# RoPi_2560.net
KiCad netlist of a schematic drawn in EAGLE
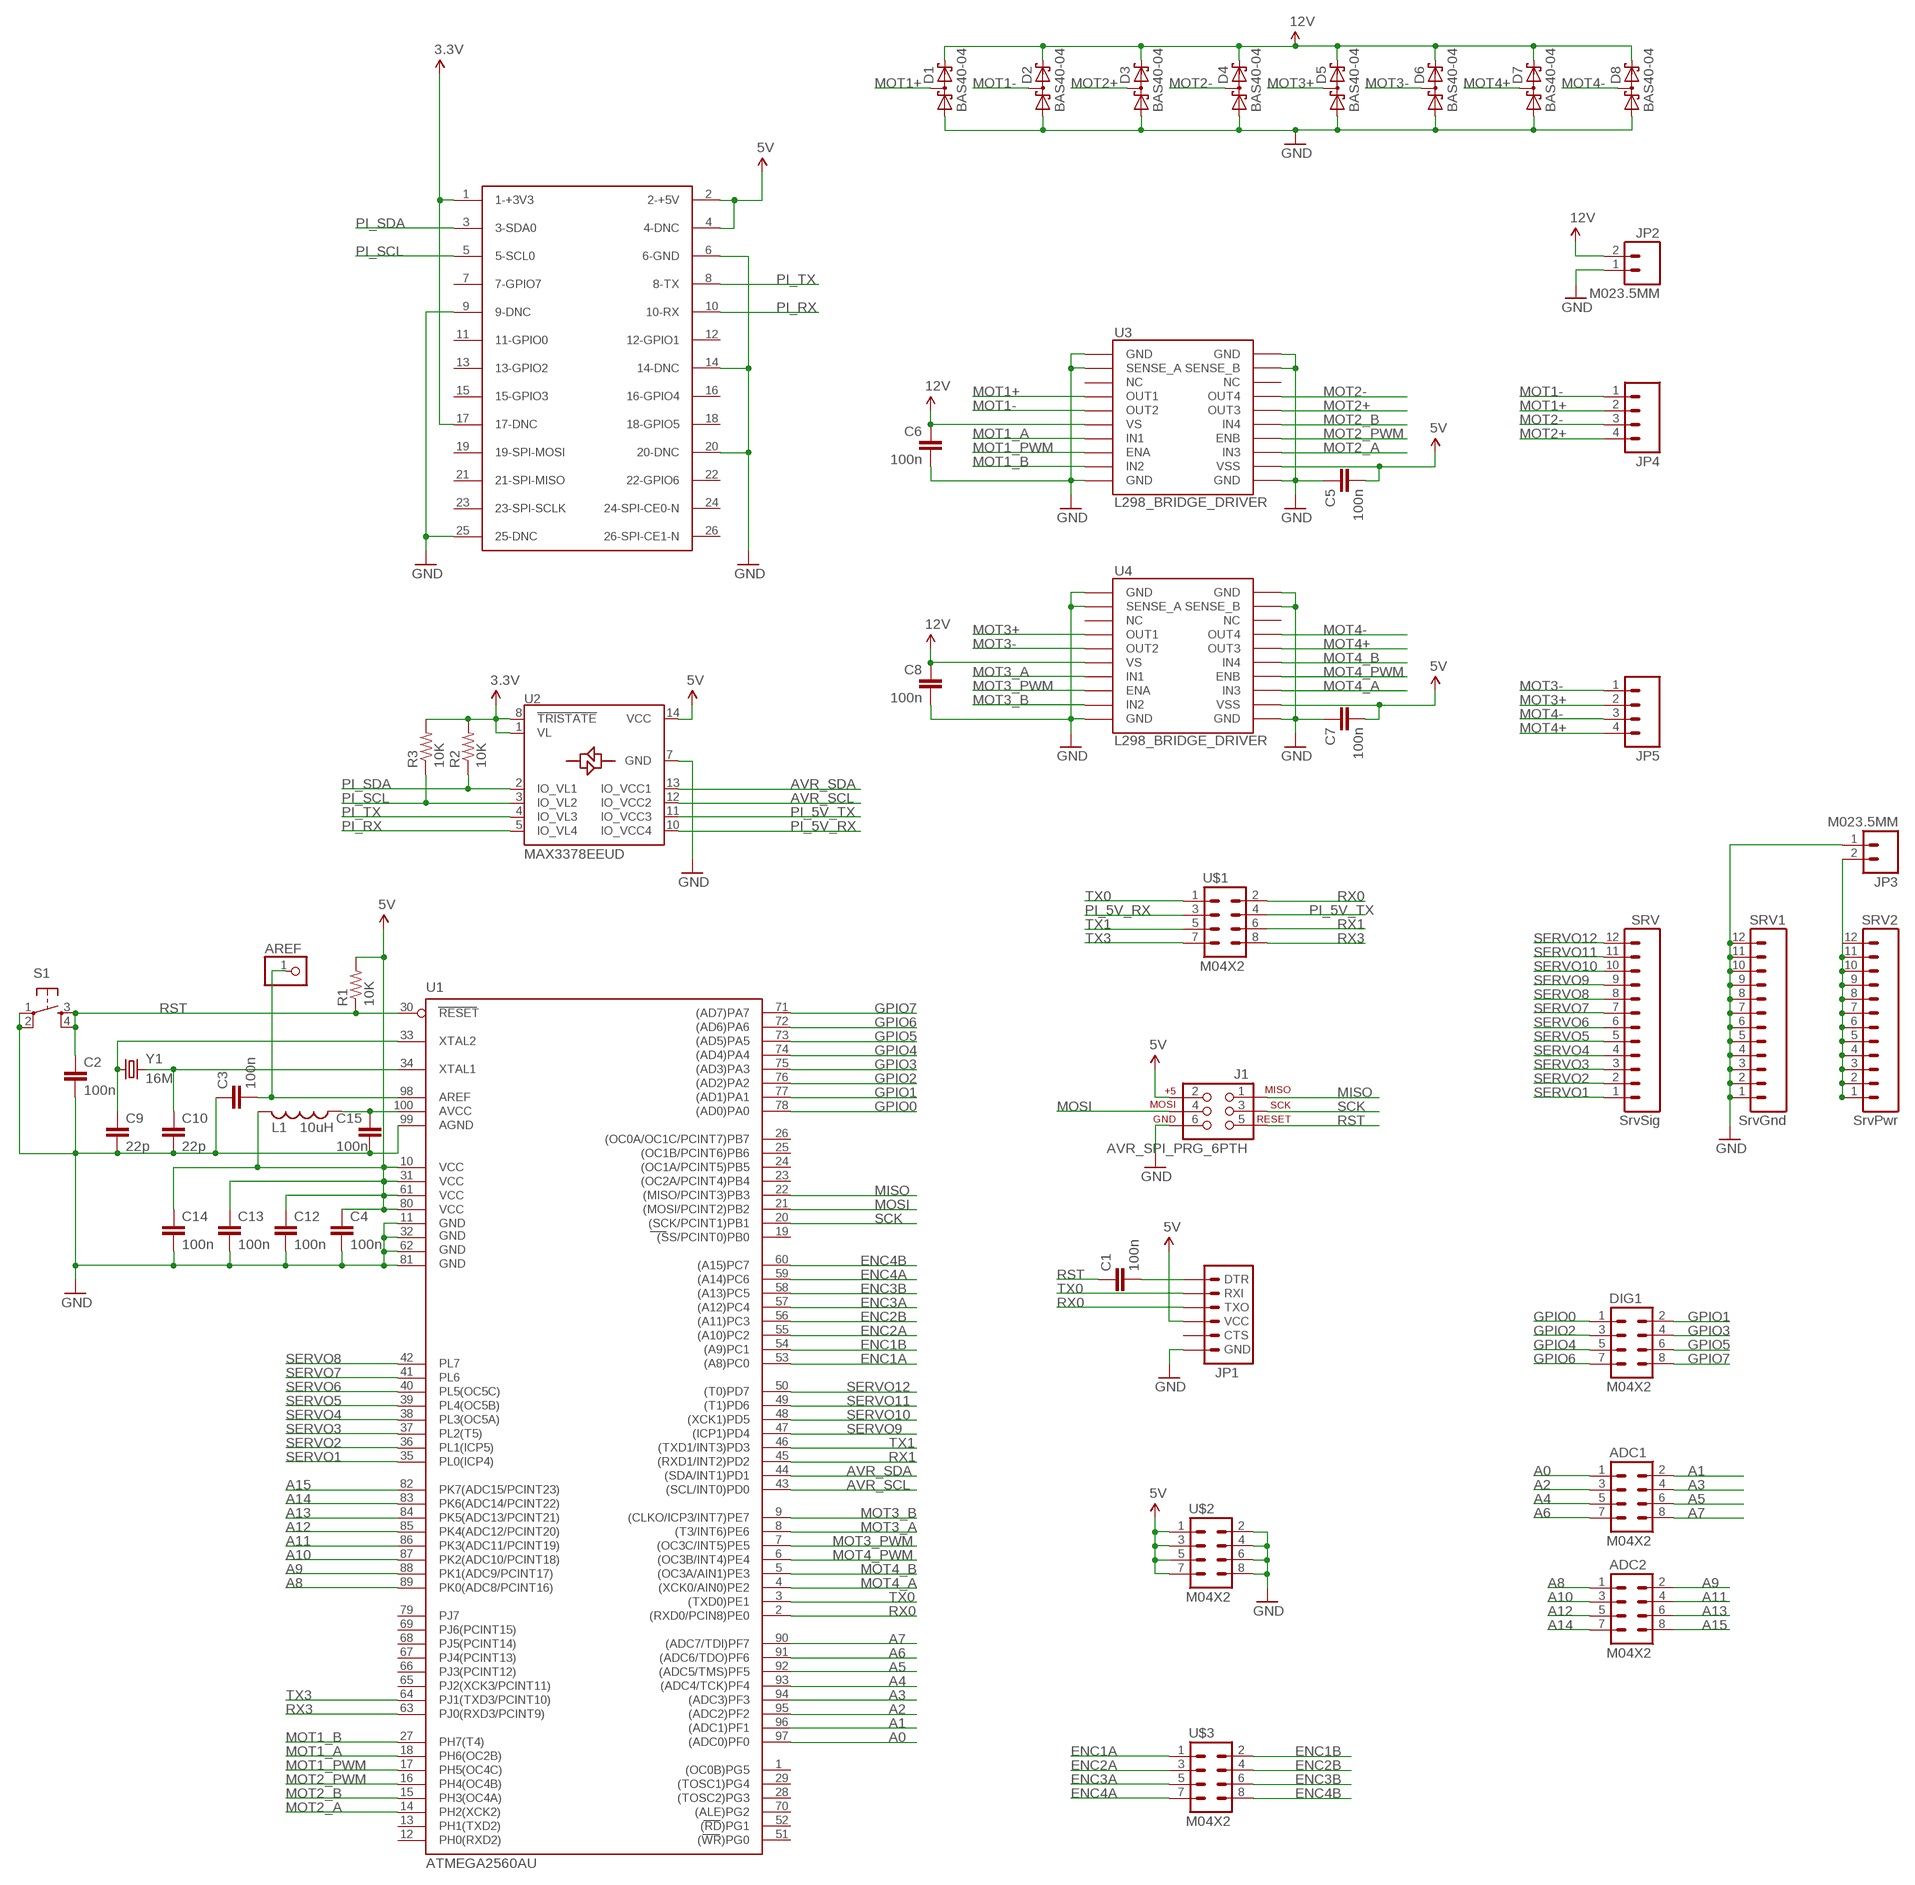
[diagram p0: schematic, sheet 1]

(export (version "E")
  (design (tool "Eeschema 10.0.6"))
  (components
    (comp (ref "ADC1")
      (value "M04X2")
      (footprint "eagle-import:2X4")
      (libsource (lib "eagle-import") (part "M04X2"))
    )
    (comp (ref "ADC2")
      (value "M04X2")
      (footprint "eagle-import:2X4")
      (libsource (lib "eagle-import") (part "M04X2"))
    )
    (comp (ref "AREF")
      (value "PINHD-1X1")
      (footprint "eagle-import:1X01")
      (libsource (lib "eagle-import") (part "PINHD-1X1"))
    )
    (comp (ref "C1")
      (value "100n")
      (footprint "eagle-import:0603-CAP")
      (libsource (lib "eagle-import") (part "CAP0603-CAP"))
    )
    (comp (ref "C2")
      (value "100n")
      (footprint "eagle-import:0603-CAP")
      (libsource (lib "eagle-import") (part "CAP0603-CAP"))
    )
    (comp (ref "C3")
      (value "100n")
      (footprint "eagle-import:0603-CAP")
      (libsource (lib "eagle-import") (part "CAP0603-CAP"))
    )
    (comp (ref "C4")
      (value "100n")
      (footprint "eagle-import:0603-CAP")
      (libsource (lib "eagle-import") (part "CAP0603-CAP"))
    )
    (comp (ref "C5")
      (value "100n")
      (footprint "eagle-import:0603-CAP")
      (libsource (lib "eagle-import") (part "CAP0603-CAP"))
    )
    (comp (ref "C6")
      (value "100n")
      (footprint "eagle-import:0603-CAP")
      (libsource (lib "eagle-import") (part "CAP0603-CAP"))
    )
    (comp (ref "C7")
      (value "100n")
      (footprint "eagle-import:0603-CAP")
      (libsource (lib "eagle-import") (part "CAP0603-CAP"))
    )
    (comp (ref "C8")
      (value "100n")
      (footprint "eagle-import:0603-CAP")
      (libsource (lib "eagle-import") (part "CAP0603-CAP"))
    )
    (comp (ref "C9")
      (value "22p")
      (footprint "eagle-import:0603-CAP")
      (libsource (lib "eagle-import") (part "CAP0603-CAP"))
    )
    (comp (ref "C10")
      (value "22p")
      (footprint "eagle-import:0603-CAP")
      (libsource (lib "eagle-import") (part "CAP0603-CAP"))
    )
    (comp (ref "C12")
      (value "100n")
      (footprint "eagle-import:0603-CAP")
      (libsource (lib "eagle-import") (part "CAP0603-CAP"))
    )
    (comp (ref "C13")
      (value "100n")
      (footprint "eagle-import:0603-CAP")
      (libsource (lib "eagle-import") (part "CAP0603-CAP"))
    )
    (comp (ref "C14")
      (value "100n")
      (footprint "eagle-import:0603-CAP")
      (libsource (lib "eagle-import") (part "CAP0603-CAP"))
    )
    (comp (ref "C15")
      (value "100n")
      (footprint "eagle-import:0603-CAP")
      (libsource (lib "eagle-import") (part "CAP0603-CAP"))
    )
    (comp (ref "D1")
      (value "BAS40-04")
      (footprint "eagle-import:SOT23")
      (libsource (lib "eagle-import") (part "BAS40-04"))
    )
    (comp (ref "D2")
      (value "BAS40-04")
      (footprint "eagle-import:SOT23")
      (libsource (lib "eagle-import") (part "BAS40-04"))
    )
    (comp (ref "D3")
      (value "BAS40-04")
      (footprint "eagle-import:SOT23")
      (libsource (lib "eagle-import") (part "BAS40-04"))
    )
    (comp (ref "D4")
      (value "BAS40-04")
      (footprint "eagle-import:SOT23")
      (libsource (lib "eagle-import") (part "BAS40-04"))
    )
    (comp (ref "D5")
      (value "BAS40-04")
      (footprint "eagle-import:SOT23")
      (libsource (lib "eagle-import") (part "BAS40-04"))
    )
    (comp (ref "D6")
      (value "BAS40-04")
      (footprint "eagle-import:SOT23")
      (libsource (lib "eagle-import") (part "BAS40-04"))
    )
    (comp (ref "D7")
      (value "BAS40-04")
      (footprint "eagle-import:SOT23")
      (libsource (lib "eagle-import") (part "BAS40-04"))
    )
    (comp (ref "D8")
      (value "BAS40-04")
      (footprint "eagle-import:SOT23")
      (libsource (lib "eagle-import") (part "BAS40-04"))
    )
    (comp (ref "DIG1")
      (value "M04X2")
      (footprint "eagle-import:2X4")
      (libsource (lib "eagle-import") (part "M04X2"))
    )
    (comp (ref "J1")
      (value "AVR_SPI_PRG_6PTH")
      (footprint "eagle-import:2X3")
      (libsource (lib "eagle-import") (part "AVR_SPI_PRG_6PTH"))
    )
    (comp (ref "JP1")
      (value "ARDUINO_SERIAL_PROGRAMSMD")
      (footprint "eagle-import:1X06-SMD")
      (libsource (lib "eagle-import") (part "ARDUINO_SERIAL_PROGRAMSMD"))
    )
    (comp (ref "JP2")
      (value "M023.5MM")
      (footprint "eagle-import:SCREWTERMINAL-3.5MM-2")
      (libsource (lib "eagle-import") (part "M023.5MM"))
    )
    (comp (ref "JP3")
      (value "M023.5MM")
      (footprint "eagle-import:SCREWTERMINAL-3.5MM-2")
      (libsource (lib "eagle-import") (part "M023.5MM"))
    )
    (comp (ref "JP4")
      (value "M04SCREW")
      (footprint "eagle-import:SCREWTERMINAL-3.5MM-4")
      (libsource (lib "eagle-import") (part "M04SCREW"))
    )
    (comp (ref "JP5")
      (value "M04SCREW")
      (footprint "eagle-import:SCREWTERMINAL-3.5MM-4")
      (libsource (lib "eagle-import") (part "M04SCREW"))
    )
    (comp (ref "L1")
      (value "10uH")
      (footprint "eagle-import:R0603")
      (libsource (lib "eagle-import") (part "L-US"))
    )
    (comp (ref "PI")
      (value "RASPBERRY-PI")
      (footprint "eagle-import:RASPBERRY-PI")
      (libsource (lib "eagle-import") (part "RASPBERRY-PI"))
    )
    (comp (ref "R1")
      (value "10K")
      (footprint "eagle-import:0603-RES")
      (libsource (lib "eagle-import") (part "RESISTOR0603-RES"))
    )
    (comp (ref "R2")
      (value "10K")
      (footprint "eagle-import:0603-RES")
      (libsource (lib "eagle-import") (part "RESISTOR0603-RES"))
    )
    (comp (ref "R3")
      (value "10K")
      (footprint "eagle-import:0603-RES")
      (libsource (lib "eagle-import") (part "RESISTOR0603-RES"))
    )
    (comp (ref "S1")
      (value "TAC_SWITCHSMD")
      (footprint "eagle-import:TACTILE_SWITCH_SMD")
      (libsource (lib "eagle-import") (part "TAC_SWITCHSMD"))
    )
    (comp (ref "SRV")
      (value "SrvSig")
      (footprint "eagle-import:1X12")
      (libsource (lib "eagle-import") (part "M12PTH"))
    )
    (comp (ref "SRV1")
      (value "SrvGnd")
      (footprint "eagle-import:1X12")
      (libsource (lib "eagle-import") (part "M12PTH"))
    )
    (comp (ref "SRV2")
      (value "SrvPwr")
      (footprint "eagle-import:1X12")
      (libsource (lib "eagle-import") (part "M12PTH"))
    )
    (comp (ref "U$1")
      (value "M04X2")
      (footprint "eagle-import:2X4")
      (libsource (lib "eagle-import") (part "M04X2"))
    )
    (comp (ref "U$2")
      (value "M04X2")
      (footprint "eagle-import:2X4")
      (libsource (lib "eagle-import") (part "M04X2"))
    )
    (comp (ref "U$3")
      (value "M04X2")
      (footprint "eagle-import:2X4")
      (libsource (lib "eagle-import") (part "M04X2"))
    )
    (comp (ref "U1")
      (value "ATMEGA2560AU")
      (footprint "eagle-import:TQFP100")
      (libsource (lib "eagle-import") (part "ATMEGA2560AU"))
    )
    (comp (ref "U2")
      (value "MAX3378EEUD")
      (footprint "eagle-import:TSSOP14")
      (libsource (lib "eagle-import") (part "MAX3378EEUD"))
    )
    (comp (ref "U3")
      (value "L298_BRIDGE_DRIVER")
      (footprint "eagle-import:POWERSO20")
      (libsource (lib "eagle-import") (part "L298_BRIDGE_DRIVER"))
    )
    (comp (ref "U4")
      (value "L298_BRIDGE_DRIVER")
      (footprint "eagle-import:POWERSO20")
      (libsource (lib "eagle-import") (part "L298_BRIDGE_DRIVER"))
    )
    (comp (ref "Y1")
      (value "16M")
      (footprint "eagle-import:HC49UP")
      (libsource (lib "eagle-import") (part "CRYSTALSMD"))
    )
  )
  (nets
    (net (code "1") (name "/A0") (class "Default")
      (node (ref "ADC1") (pin "1") (pinfunction "1_1") (pintype "passive"))
      (node (ref "U1") (pin "97") (pinfunction "(ADC0)PF0_97") (pintype "bidirectional"))
    )
    (net (code "2") (name "/A1") (class "Default")
      (node (ref "ADC1") (pin "2") (pinfunction "2_2") (pintype "passive"))
      (node (ref "U1") (pin "96") (pinfunction "(ADC1)PF1_96") (pintype "bidirectional"))
    )
    (net (code "3") (name "/A2") (class "Default")
      (node (ref "ADC1") (pin "3") (pinfunction "3_3") (pintype "passive"))
      (node (ref "U1") (pin "95") (pinfunction "(ADC2)PF2_95") (pintype "bidirectional"))
    )
    (net (code "4") (name "/A3") (class "Default")
      (node (ref "ADC1") (pin "4") (pinfunction "4_4") (pintype "passive"))
      (node (ref "U1") (pin "94") (pinfunction "(ADC3)PF3_94") (pintype "bidirectional"))
    )
    (net (code "5") (name "/A4") (class "Default")
      (node (ref "ADC1") (pin "5") (pinfunction "5_5") (pintype "passive"))
      (node (ref "U1") (pin "93") (pinfunction "(ADC4/TCK)PF4_93") (pintype "bidirectional"))
    )
    (net (code "6") (name "/A5") (class "Default")
      (node (ref "ADC1") (pin "6") (pinfunction "6_6") (pintype "passive"))
      (node (ref "U1") (pin "92") (pinfunction "(ADC5/TMS)PF5_92") (pintype "bidirectional"))
    )
    (net (code "7") (name "/A6") (class "Default")
      (node (ref "ADC1") (pin "7") (pinfunction "7_7") (pintype "passive"))
      (node (ref "U1") (pin "91") (pinfunction "(ADC6/TDO)PF6_91") (pintype "bidirectional"))
    )
    (net (code "8") (name "/A7") (class "Default")
      (node (ref "ADC1") (pin "8") (pinfunction "8_8") (pintype "passive"))
      (node (ref "U1") (pin "90") (pinfunction "(ADC7/TDI)PF7_90") (pintype "bidirectional"))
    )
    (net (code "9") (name "/A8") (class "Default")
      (node (ref "ADC2") (pin "1") (pinfunction "1_1") (pintype "passive"))
      (node (ref "U1") (pin "89") (pinfunction "PK0(ADC8/PCINT16)_89") (pintype "bidirectional"))
    )
    (net (code "10") (name "/A9") (class "Default")
      (node (ref "ADC2") (pin "2") (pinfunction "2_2") (pintype "passive"))
      (node (ref "U1") (pin "88") (pinfunction "PK1(ADC9/PCINT17)_88") (pintype "bidirectional"))
    )
    (net (code "11") (name "/A10") (class "Default")
      (node (ref "ADC2") (pin "3") (pinfunction "3_3") (pintype "passive"))
      (node (ref "U1") (pin "87") (pinfunction "PK2(ADC10/PCINT18)_87") (pintype "bidirectional"))
    )
    (net (code "12") (name "/A11") (class "Default")
      (node (ref "ADC2") (pin "4") (pinfunction "4_4") (pintype "passive"))
      (node (ref "U1") (pin "86") (pinfunction "PK3(ADC11/PCINT19)_86") (pintype "bidirectional"))
    )
    (net (code "13") (name "/A12") (class "Default")
      (node (ref "ADC2") (pin "5") (pinfunction "5_5") (pintype "passive"))
      (node (ref "U1") (pin "85") (pinfunction "PK4(ADC12/PCINT20)_85") (pintype "bidirectional"))
    )
    (net (code "14") (name "/A13") (class "Default")
      (node (ref "ADC2") (pin "6") (pinfunction "6_6") (pintype "passive"))
      (node (ref "U1") (pin "84") (pinfunction "PK5(ADC13/PCINT21)_84") (pintype "bidirectional"))
    )
    (net (code "15") (name "/A14") (class "Default")
      (node (ref "ADC2") (pin "7") (pinfunction "7_7") (pintype "passive"))
      (node (ref "U1") (pin "83") (pinfunction "PK6(ADC14/PCINT22)_83") (pintype "bidirectional"))
    )
    (net (code "16") (name "/A15") (class "Default")
      (node (ref "ADC2") (pin "8") (pinfunction "8_8") (pintype "passive"))
      (node (ref "U1") (pin "82") (pinfunction "PK7(ADC15/PCINT23)_82") (pintype "bidirectional"))
    )
    (net (code "17") (name "/AVR_SCL") (class "Default")
      (node (ref "U1") (pin "43") (pinfunction "(SCL/INT0)PD0_43") (pintype "bidirectional"))
      (node (ref "U2") (pin "12") (pinfunction "IO_VCC2_12") (pintype "bidirectional"))
    )
    (net (code "18") (name "/AVR_SDA") (class "Default")
      (node (ref "U1") (pin "44") (pinfunction "(SDA/INT1)PD1_44") (pintype "bidirectional"))
      (node (ref "U2") (pin "13") (pinfunction "IO_VCC1_13") (pintype "bidirectional"))
    )
    (net (code "19") (name "/ENC1A") (class "Default")
      (node (ref "U$3") (pin "1") (pinfunction "1_1") (pintype "passive"))
      (node (ref "U1") (pin "53") (pinfunction "(A8)PC0_53") (pintype "bidirectional"))
    )
    (net (code "20") (name "/ENC1B") (class "Default")
      (node (ref "U$3") (pin "2") (pinfunction "2_2") (pintype "passive"))
      (node (ref "U1") (pin "54") (pinfunction "(A9)PC1_54") (pintype "bidirectional"))
    )
    (net (code "21") (name "/ENC2A") (class "Default")
      (node (ref "U$3") (pin "3") (pinfunction "3_3") (pintype "passive"))
      (node (ref "U1") (pin "55") (pinfunction "(A10)PC2_55") (pintype "bidirectional"))
    )
    (net (code "22") (name "/ENC2B") (class "Default")
      (node (ref "U$3") (pin "4") (pinfunction "4_4") (pintype "passive"))
      (node (ref "U1") (pin "56") (pinfunction "(A11)PC3_56") (pintype "bidirectional"))
    )
    (net (code "23") (name "/ENC3A") (class "Default")
      (node (ref "U$3") (pin "5") (pinfunction "5_5") (pintype "passive"))
      (node (ref "U1") (pin "57") (pinfunction "(A12)PC4_57") (pintype "bidirectional"))
    )
    (net (code "24") (name "/ENC3B") (class "Default")
      (node (ref "U$3") (pin "6") (pinfunction "6_6") (pintype "passive"))
      (node (ref "U1") (pin "58") (pinfunction "(A13)PC5_58") (pintype "bidirectional"))
    )
    (net (code "25") (name "/ENC4A") (class "Default")
      (node (ref "U$3") (pin "7") (pinfunction "7_7") (pintype "passive"))
      (node (ref "U1") (pin "59") (pinfunction "(A14)PC6_59") (pintype "bidirectional"))
    )
    (net (code "26") (name "/ENC4B") (class "Default")
      (node (ref "U$3") (pin "8") (pinfunction "8_8") (pintype "passive"))
      (node (ref "U1") (pin "60") (pinfunction "(A15)PC7_60") (pintype "bidirectional"))
    )
    (net (code "27") (name "/GPIO0") (class "Default")
      (node (ref "DIG1") (pin "1") (pinfunction "1_1") (pintype "passive"))
      (node (ref "U1") (pin "78") (pinfunction "(AD0)PA0_78") (pintype "bidirectional"))
    )
    (net (code "28") (name "/GPIO1") (class "Default")
      (node (ref "DIG1") (pin "2") (pinfunction "2_2") (pintype "passive"))
      (node (ref "U1") (pin "77") (pinfunction "(AD1)PA1_77") (pintype "bidirectional"))
    )
    (net (code "29") (name "/GPIO2") (class "Default")
      (node (ref "DIG1") (pin "3") (pinfunction "3_3") (pintype "passive"))
      (node (ref "U1") (pin "76") (pinfunction "(AD2)PA2_76") (pintype "bidirectional"))
    )
    (net (code "30") (name "/GPIO3") (class "Default")
      (node (ref "DIG1") (pin "4") (pinfunction "4_4") (pintype "passive"))
      (node (ref "U1") (pin "75") (pinfunction "(AD3)PA3_75") (pintype "bidirectional"))
    )
    (net (code "31") (name "/GPIO4") (class "Default")
      (node (ref "DIG1") (pin "5") (pinfunction "5_5") (pintype "passive"))
      (node (ref "U1") (pin "74") (pinfunction "(AD4)PA4_74") (pintype "bidirectional"))
    )
    (net (code "32") (name "/GPIO5") (class "Default")
      (node (ref "DIG1") (pin "6") (pinfunction "6_6") (pintype "passive"))
      (node (ref "U1") (pin "73") (pinfunction "(AD5)PA5_73") (pintype "bidirectional"))
    )
    (net (code "33") (name "/GPIO6") (class "Default")
      (node (ref "DIG1") (pin "7") (pinfunction "7_7") (pintype "passive"))
      (node (ref "U1") (pin "72") (pinfunction "(AD6)PA6_72") (pintype "bidirectional"))
    )
    (net (code "34") (name "/GPIO7") (class "Default")
      (node (ref "DIG1") (pin "8") (pinfunction "8_8") (pintype "passive"))
      (node (ref "U1") (pin "71") (pinfunction "(AD7)PA7_71") (pintype "bidirectional"))
    )
    (net (code "35") (name "/MISO") (class "Default")
      (node (ref "J1") (pin "1") (pinfunction "1_1") (pintype "passive"))
      (node (ref "U1") (pin "22") (pinfunction "(MISO/PCINT3)PB3_22") (pintype "bidirectional"))
    )
    (net (code "36") (name "/MOSI") (class "Default")
      (node (ref "J1") (pin "4") (pinfunction "4_4") (pintype "passive"))
      (node (ref "U1") (pin "21") (pinfunction "(MOSI/PCINT2)PB2_21") (pintype "bidirectional"))
    )
    (net (code "37") (name "/MOT1+") (class "Default")
      (node (ref "D1") (pin "3") (pinfunction "C1A2_3") (pintype "passive"))
      (node (ref "JP4") (pin "2") (pinfunction "2_2") (pintype "passive"))
      (node (ref "U3") (pin "4") (pinfunction "OUT1_4") (pintype "bidirectional"))
    )
    (net (code "38") (name "/MOT1-") (class "Default")
      (node (ref "D2") (pin "3") (pinfunction "C1A2_3") (pintype "passive"))
      (node (ref "JP4") (pin "1") (pinfunction "1_1") (pintype "passive"))
      (node (ref "U3") (pin "5") (pinfunction "OUT2_5") (pintype "bidirectional"))
    )
    (net (code "39") (name "/MOT1_A") (class "Default")
      (node (ref "U1") (pin "18") (pinfunction "PH6(OC2B)_18") (pintype "bidirectional"))
      (node (ref "U3") (pin "7") (pinfunction "IN1_7") (pintype "bidirectional"))
    )
    (net (code "40") (name "/MOT1_B") (class "Default")
      (node (ref "U1") (pin "27") (pinfunction "PH7(T4)_27") (pintype "bidirectional"))
      (node (ref "U3") (pin "9") (pinfunction "IN2_9") (pintype "bidirectional"))
    )
    (net (code "41") (name "/MOT1_PWM") (class "Default")
      (node (ref "U1") (pin "17") (pinfunction "PH5(OC4C)_17") (pintype "bidirectional"))
      (node (ref "U3") (pin "8") (pinfunction "ENA_8") (pintype "bidirectional"))
    )
    (net (code "42") (name "/MOT2+") (class "Default")
      (node (ref "D3") (pin "3") (pinfunction "C1A2_3") (pintype "passive"))
      (node (ref "JP4") (pin "4") (pinfunction "4_4") (pintype "passive"))
      (node (ref "U3") (pin "16") (pinfunction "OUT3_16") (pintype "bidirectional"))
    )
    (net (code "43") (name "/MOT2-") (class "Default")
      (node (ref "D4") (pin "3") (pinfunction "C1A2_3") (pintype "passive"))
      (node (ref "JP4") (pin "3") (pinfunction "3_3") (pintype "passive"))
      (node (ref "U3") (pin "17") (pinfunction "OUT4_17") (pintype "bidirectional"))
    )
    (net (code "44") (name "/MOT2_A") (class "Default")
      (node (ref "U1") (pin "14") (pinfunction "PH2(XCK2)_14") (pintype "bidirectional"))
      (node (ref "U3") (pin "13") (pinfunction "IN3_13") (pintype "bidirectional"))
    )
    (net (code "45") (name "/MOT2_B") (class "Default")
      (node (ref "U1") (pin "15") (pinfunction "PH3(OC4A)_15") (pintype "bidirectional"))
      (node (ref "U3") (pin "15") (pinfunction "IN4_15") (pintype "bidirectional"))
    )
    (net (code "46") (name "/MOT2_PWM") (class "Default")
      (node (ref "U1") (pin "16") (pinfunction "PH4(OC4B)_16") (pintype "bidirectional"))
      (node (ref "U3") (pin "14") (pinfunction "ENB_14") (pintype "bidirectional"))
    )
    (net (code "47") (name "/MOT3+") (class "Default")
      (node (ref "D5") (pin "3") (pinfunction "C1A2_3") (pintype "passive"))
      (node (ref "JP5") (pin "2") (pinfunction "2_2") (pintype "passive"))
      (node (ref "U4") (pin "4") (pinfunction "OUT1_4") (pintype "bidirectional"))
    )
    (net (code "48") (name "/MOT3-") (class "Default")
      (node (ref "D6") (pin "3") (pinfunction "C1A2_3") (pintype "passive"))
      (node (ref "JP5") (pin "1") (pinfunction "1_1") (pintype "passive"))
      (node (ref "U4") (pin "5") (pinfunction "OUT2_5") (pintype "bidirectional"))
    )
    (net (code "49") (name "/MOT3_A") (class "Default")
      (node (ref "U1") (pin "8") (pinfunction "(T3/INT6)PE6_8") (pintype "bidirectional"))
      (node (ref "U4") (pin "7") (pinfunction "IN1_7") (pintype "bidirectional"))
    )
    (net (code "50") (name "/MOT3_B") (class "Default")
      (node (ref "U1") (pin "9") (pinfunction "(CLKO/ICP3/INT7)PE7_9") (pintype "bidirectional"))
      (node (ref "U4") (pin "9") (pinfunction "IN2_9") (pintype "bidirectional"))
    )
    (net (code "51") (name "/MOT3_PWM") (class "Default")
      (node (ref "U1") (pin "7") (pinfunction "(OC3C/INT5)PE5_7") (pintype "bidirectional"))
      (node (ref "U4") (pin "8") (pinfunction "ENA_8") (pintype "bidirectional"))
    )
    (net (code "52") (name "/MOT4+") (class "Default")
      (node (ref "D7") (pin "3") (pinfunction "C1A2_3") (pintype "passive"))
      (node (ref "JP5") (pin "4") (pinfunction "4_4") (pintype "passive"))
      (node (ref "U4") (pin "16") (pinfunction "OUT3_16") (pintype "bidirectional"))
    )
    (net (code "53") (name "/MOT4-") (class "Default")
      (node (ref "D8") (pin "3") (pinfunction "C1A2_3") (pintype "passive"))
      (node (ref "JP5") (pin "3") (pinfunction "3_3") (pintype "passive"))
      (node (ref "U4") (pin "17") (pinfunction "OUT4_17") (pintype "bidirectional"))
    )
    (net (code "54") (name "/MOT4_A") (class "Default")
      (node (ref "U1") (pin "4") (pinfunction "(XCK0/AIN0)PE2_4") (pintype "bidirectional"))
      (node (ref "U4") (pin "13") (pinfunction "IN3_13") (pintype "bidirectional"))
    )
    (net (code "55") (name "/MOT4_B") (class "Default")
      (node (ref "U1") (pin "5") (pinfunction "(OC3A/AIN1)PE3_5") (pintype "bidirectional"))
      (node (ref "U4") (pin "15") (pinfunction "IN4_15") (pintype "bidirectional"))
    )
    (net (code "56") (name "/MOT4_PWM") (class "Default")
      (node (ref "U1") (pin "6") (pinfunction "(OC3B/INT4)PE4_6") (pintype "bidirectional"))
      (node (ref "U4") (pin "14") (pinfunction "ENB_14") (pintype "bidirectional"))
    )
    (net (code "57") (name "/PI_5V_RX") (class "Default")
      (node (ref "U$1") (pin "3") (pinfunction "3_3") (pintype "passive"))
      (node (ref "U2") (pin "10") (pinfunction "IO_VCC4_10") (pintype "bidirectional"))
    )
    (net (code "58") (name "/PI_5V_TX") (class "Default")
      (node (ref "U$1") (pin "4") (pinfunction "4_4") (pintype "passive"))
      (node (ref "U2") (pin "11") (pinfunction "IO_VCC3_11") (pintype "bidirectional"))
    )
    (net (code "59") (name "/PI_RX") (class "Default")
      (node (ref "PI") (pin "10") (pinfunction "10-RX_10") (pintype "bidirectional"))
      (node (ref "U2") (pin "5") (pinfunction "IO_VL4_5") (pintype "bidirectional"))
    )
    (net (code "60") (name "/PI_SCL") (class "Default")
      (node (ref "PI") (pin "5") (pinfunction "5-SCL0_5") (pintype "bidirectional"))
      (node (ref "R3") (pin "1") (pinfunction "1_1") (pintype "passive"))
      (node (ref "U2") (pin "3") (pinfunction "IO_VL2_3") (pintype "bidirectional"))
    )
    (net (code "61") (name "/PI_SDA") (class "Default")
      (node (ref "PI") (pin "3") (pinfunction "3-SDA0_3") (pintype "bidirectional"))
      (node (ref "R2") (pin "1") (pinfunction "1_1") (pintype "passive"))
      (node (ref "U2") (pin "2") (pinfunction "IO_VL1_2") (pintype "bidirectional"))
    )
    (net (code "62") (name "/PI_TX") (class "Default")
      (node (ref "PI") (pin "8") (pinfunction "8-TX_8") (pintype "bidirectional"))
      (node (ref "U2") (pin "4") (pinfunction "IO_VL3_4") (pintype "bidirectional"))
    )
    (net (code "63") (name "/RST") (class "Default")
      (node (ref "C1") (pin "1") (pinfunction "1_1") (pintype "passive"))
      (node (ref "C2") (pin "1") (pinfunction "1_1") (pintype "passive"))
      (node (ref "J1") (pin "5") (pinfunction "5_5") (pintype "passive"))
      (node (ref "R1") (pin "1") (pinfunction "1_1") (pintype "passive"))
      (node (ref "S1") (pin "3") (pinfunction "3_3") (pintype "passive"))
      (node (ref "S1") (pin "4") (pinfunction "4_4") (pintype "passive"))
      (node (ref "U1") (pin "30") (pinfunction "RESET_30") (pintype "input"))
    )
    (net (code "64") (name "/RX0") (class "Default")
      (node (ref "JP1") (pin "3") (pinfunction "TXO_3") (pintype "passive"))
      (node (ref "U$1") (pin "2") (pinfunction "2_2") (pintype "passive"))
      (node (ref "U1") (pin "2") (pinfunction "(RXD0/PCIN8)PE0_2") (pintype "bidirectional"))
    )
    (net (code "65") (name "/RX1") (class "Default")
      (node (ref "U$1") (pin "6") (pinfunction "6_6") (pintype "passive"))
      (node (ref "U1") (pin "45") (pinfunction "(RXD1/INT2)PD2_45") (pintype "bidirectional"))
    )
    (net (code "66") (name "/RX3") (class "Default")
      (node (ref "U$1") (pin "8") (pinfunction "8_8") (pintype "passive"))
      (node (ref "U1") (pin "63") (pinfunction "PJ0(RXD3/PCINT9)_63") (pintype "bidirectional"))
    )
    (net (code "67") (name "/SCK") (class "Default")
      (node (ref "J1") (pin "3") (pinfunction "3_3") (pintype "passive"))
      (node (ref "U1") (pin "20") (pinfunction "(SCK/PCINT1)PB1_20") (pintype "bidirectional"))
    )
    (net (code "68") (name "/SERVO1") (class "Default")
      (node (ref "SRV") (pin "1") (pinfunction "1_1") (pintype "passive"))
      (node (ref "U1") (pin "35") (pinfunction "PL0(ICP4)_35") (pintype "bidirectional"))
    )
    (net (code "69") (name "/SERVO2") (class "Default")
      (node (ref "SRV") (pin "2") (pinfunction "2_2") (pintype "passive"))
      (node (ref "U1") (pin "36") (pinfunction "PL1(ICP5)_36") (pintype "bidirectional"))
    )
    (net (code "70") (name "/SERVO3") (class "Default")
      (node (ref "SRV") (pin "3") (pinfunction "3_3") (pintype "passive"))
      (node (ref "U1") (pin "37") (pinfunction "PL2(T5)_37") (pintype "bidirectional"))
    )
    (net (code "71") (name "/SERVO4") (class "Default")
      (node (ref "SRV") (pin "4") (pinfunction "4_4") (pintype "passive"))
      (node (ref "U1") (pin "38") (pinfunction "PL3(OC5A)_38") (pintype "bidirectional"))
    )
    (net (code "72") (name "/SERVO5") (class "Default")
      (node (ref "SRV") (pin "5") (pinfunction "5_5") (pintype "passive"))
      (node (ref "U1") (pin "39") (pinfunction "PL4(OC5B)_39") (pintype "bidirectional"))
    )
    (net (code "73") (name "/SERVO6") (class "Default")
      (node (ref "SRV") (pin "6") (pinfunction "6_6") (pintype "passive"))
      (node (ref "U1") (pin "40") (pinfunction "PL5(OC5C)_40") (pintype "bidirectional"))
    )
    (net (code "74") (name "/SERVO7") (class "Default")
      (node (ref "SRV") (pin "7") (pinfunction "7_7") (pintype "passive"))
      (node (ref "U1") (pin "41") (pinfunction "PL6_41") (pintype "bidirectional"))
    )
    (net (code "75") (name "/SERVO8") (class "Default")
      (node (ref "SRV") (pin "8") (pinfunction "8_8") (pintype "passive"))
      (node (ref "U1") (pin "42") (pinfunction "PL7_42") (pintype "bidirectional"))
    )
    (net (code "76") (name "/SERVO9") (class "Default")
      (node (ref "SRV") (pin "9") (pinfunction "9_9") (pintype "passive"))
      (node (ref "U1") (pin "47") (pinfunction "(ICP1)PD4_47") (pintype "bidirectional"))
    )
    (net (code "77") (name "/SERVO10") (class "Default")
      (node (ref "SRV") (pin "10") (pinfunction "10_10") (pintype "passive"))
      (node (ref "U1") (pin "48") (pinfunction "(XCK1)PD5_48") (pintype "bidirectional"))
    )
    (net (code "78") (name "/SERVO11") (class "Default")
      (node (ref "SRV") (pin "11") (pinfunction "11_11") (pintype "passive"))
      (node (ref "U1") (pin "49") (pinfunction "(T1)PD6_49") (pintype "bidirectional"))
    )
    (net (code "79") (name "/SERVO12") (class "Default")
      (node (ref "SRV") (pin "12") (pinfunction "12_12") (pintype "passive"))
      (node (ref "U1") (pin "50") (pinfunction "(T0)PD7_50") (pintype "bidirectional"))
    )
    (net (code "80") (name "/TX0") (class "Default")
      (node (ref "JP1") (pin "2") (pinfunction "RXI_2") (pintype "passive"))
      (node (ref "U$1") (pin "1") (pinfunction "1_1") (pintype "passive"))
      (node (ref "U1") (pin "3") (pinfunction "(TXD0)PE1_3") (pintype "bidirectional"))
    )
    (net (code "81") (name "/TX1") (class "Default")
      (node (ref "U$1") (pin "5") (pinfunction "5_5") (pintype "passive"))
      (node (ref "U1") (pin "46") (pinfunction "(TXD1/INT3)PD3_46") (pintype "bidirectional"))
    )
    (net (code "82") (name "/TX3") (class "Default")
      (node (ref "U$1") (pin "7") (pinfunction "7_7") (pintype "passive"))
      (node (ref "U1") (pin "64") (pinfunction "PJ1(TXD3/PCINT10)_64") (pintype "bidirectional"))
    )
    (net (code "83") (name "3.3V") (class "Default")
      (node (ref "PI") (pin "1") (pinfunction "1-+3V3_1") (pintype "bidirectional"))
      (node (ref "PI") (pin "17") (pinfunction "17-DNC_17") (pintype "bidirectional"))
      (node (ref "R2") (pin "2") (pinfunction "2_2") (pintype "passive"))
      (node (ref "R3") (pin "2") (pinfunction "2_2") (pintype "passive"))
      (node (ref "U2") (pin "1") (pinfunction "VL_1") (pintype "power_in"))
      (node (ref "U2") (pin "8") (pinfunction "~{TRISTATE}_8") (pintype "input"))
    )
    (net (code "84") (name "5V") (class "Default")
      (node (ref "C12") (pin "1") (pinfunction "1_1") (pintype "passive"))
      (node (ref "C13") (pin "1") (pinfunction "1_1") (pintype "passive"))
      (node (ref "C14") (pin "1") (pinfunction "1_1") (pintype "passive"))
      (node (ref "C4") (pin "1") (pinfunction "1_1") (pintype "passive"))
      (node (ref "C5") (pin "2") (pinfunction "2_2") (pintype "passive"))
      (node (ref "C7") (pin "2") (pinfunction "2_2") (pintype "passive"))
      (node (ref "J1") (pin "2") (pinfunction "2_2") (pintype "passive"))
      (node (ref "JP1") (pin "4") (pinfunction "VCC_4") (pintype "passive"))
      (node (ref "L1") (pin "2") (pinfunction "2_2") (pintype "passive"))
      (node (ref "PI") (pin "2") (pinfunction "2-+5V_2") (pintype "bidirectional"))
      (node (ref "PI") (pin "4") (pinfunction "4-DNC_4") (pintype "bidirectional"))
      (node (ref "R1") (pin "2") (pinfunction "2_2") (pintype "passive"))
      (node (ref "U$2") (pin "1") (pinfunction "1_1") (pintype "passive"))
      (node (ref "U$2") (pin "3") (pinfunction "3_3") (pintype "passive"))
      (node (ref "U$2") (pin "5") (pinfunction "5_5") (pintype "passive"))
      (node (ref "U$2") (pin "7") (pinfunction "7_7") (pintype "passive"))
      (node (ref "U1") (pin "10") (pinfunction "VCC_10") (pintype "power_in"))
      (node (ref "U1") (pin "31") (pinfunction "VCC1_31") (pintype "power_in"))
      (node (ref "U1") (pin "61") (pinfunction "VCC2_61") (pintype "power_in"))
      (node (ref "U1") (pin "80") (pinfunction "VCC3_80") (pintype "power_in"))
      (node (ref "U2") (pin "14") (pinfunction "VCC_14") (pintype "power_in"))
      (node (ref "U3") (pin "12") (pinfunction "VSS_12") (pintype "bidirectional"))
      (node (ref "U4") (pin "12") (pinfunction "VSS_12") (pintype "bidirectional"))
    )
    (net (code "85") (name "12V") (class "Default")
      (node (ref "C6") (pin "1") (pinfunction "1_1") (pintype "passive"))
      (node (ref "C8") (pin "1") (pinfunction "1_1") (pintype "passive"))
      (node (ref "D1") (pin "2") (pinfunction "C2_2") (pintype "passive"))
      (node (ref "D2") (pin "2") (pinfunction "C2_2") (pintype "passive"))
      (node (ref "D3") (pin "2") (pinfunction "C2_2") (pintype "passive"))
      (node (ref "D4") (pin "2") (pinfunction "C2_2") (pintype "passive"))
      (node (ref "D5") (pin "2") (pinfunction "C2_2") (pintype "passive"))
      (node (ref "D6") (pin "2") (pinfunction "C2_2") (pintype "passive"))
      (node (ref "D7") (pin "2") (pinfunction "C2_2") (pintype "passive"))
      (node (ref "D8") (pin "2") (pinfunction "C2_2") (pintype "passive"))
      (node (ref "JP2") (pin "2") (pinfunction "2_2") (pintype "passive"))
      (node (ref "U3") (pin "6") (pinfunction "VS_6") (pintype "bidirectional"))
      (node (ref "U4") (pin "6") (pinfunction "VS_6") (pintype "bidirectional"))
    )
    (net (code "86") (name "GND") (class "Default")
      (node (ref "C10") (pin "2") (pinfunction "2_2") (pintype "passive"))
      (node (ref "C12") (pin "2") (pinfunction "2_2") (pintype "passive"))
      (node (ref "C13") (pin "2") (pinfunction "2_2") (pintype "passive"))
      (node (ref "C14") (pin "2") (pinfunction "2_2") (pintype "passive"))
      (node (ref "C15") (pin "2") (pinfunction "2_2") (pintype "passive"))
      (node (ref "C2") (pin "2") (pinfunction "2_2") (pintype "passive"))
      (node (ref "C3") (pin "1") (pinfunction "1_1") (pintype "passive"))
      (node (ref "C4") (pin "2") (pinfunction "2_2") (pintype "passive"))
      (node (ref "C5") (pin "1") (pinfunction "1_1") (pintype "passive"))
      (node (ref "C6") (pin "2") (pinfunction "2_2") (pintype "passive"))
      (node (ref "C7") (pin "1") (pinfunction "1_1") (pintype "passive"))
      (node (ref "C8") (pin "2") (pinfunction "2_2") (pintype "passive"))
      (node (ref "C9") (pin "2") (pinfunction "2_2") (pintype "passive"))
      (node (ref "D1") (pin "1") (pinfunction "A1_1") (pintype "passive"))
      (node (ref "D2") (pin "1") (pinfunction "A1_1") (pintype "passive"))
      (node (ref "D3") (pin "1") (pinfunction "A1_1") (pintype "passive"))
      (node (ref "D4") (pin "1") (pinfunction "A1_1") (pintype "passive"))
      (node (ref "D5") (pin "1") (pinfunction "A1_1") (pintype "passive"))
      (node (ref "D6") (pin "1") (pinfunction "A1_1") (pintype "passive"))
      (node (ref "D7") (pin "1") (pinfunction "A1_1") (pintype "passive"))
      (node (ref "D8") (pin "1") (pinfunction "A1_1") (pintype "passive"))
      (node (ref "J1") (pin "6") (pinfunction "6_6") (pintype "passive"))
      (node (ref "JP1") (pin "6") (pinfunction "GND_6") (pintype "passive"))
      (node (ref "JP2") (pin "1") (pinfunction "1_1") (pintype "passive"))
      (node (ref "JP3") (pin "1") (pinfunction "1_1") (pintype "passive"))
      (node (ref "PI") (pin "14") (pinfunction "14-DNC_14") (pintype "bidirectional"))
      (node (ref "PI") (pin "20") (pinfunction "20-DNC_20") (pintype "bidirectional"))
      (node (ref "PI") (pin "25") (pinfunction "25-DNC_25") (pintype "bidirectional"))
      (node (ref "PI") (pin "6") (pinfunction "6-GND_6") (pintype "bidirectional"))
      (node (ref "PI") (pin "9") (pinfunction "9-DNC_9") (pintype "bidirectional"))
      (node (ref "S1") (pin "1") (pinfunction "1_1") (pintype "passive"))
      (node (ref "S1") (pin "2") (pinfunction "2_2") (pintype "passive"))
      (node (ref "SRV1") (pin "1") (pinfunction "1_1") (pintype "passive"))
      (node (ref "SRV1") (pin "10") (pinfunction "10_10") (pintype "passive"))
      (node (ref "SRV1") (pin "11") (pinfunction "11_11") (pintype "passive"))
      (node (ref "SRV1") (pin "12") (pinfunction "12_12") (pintype "passive"))
      (node (ref "SRV1") (pin "2") (pinfunction "2_2") (pintype "passive"))
      (node (ref "SRV1") (pin "3") (pinfunction "3_3") (pintype "passive"))
      (node (ref "SRV1") (pin "4") (pinfunction "4_4") (pintype "passive"))
      (node (ref "SRV1") (pin "5") (pinfunction "5_5") (pintype "passive"))
      (node (ref "SRV1") (pin "6") (pinfunction "6_6") (pintype "passive"))
      (node (ref "SRV1") (pin "7") (pinfunction "7_7") (pintype "passive"))
      (node (ref "SRV1") (pin "8") (pinfunction "8_8") (pintype "passive"))
      (node (ref "SRV1") (pin "9") (pinfunction "9_9") (pintype "passive"))
      (node (ref "U$2") (pin "2") (pinfunction "2_2") (pintype "passive"))
      (node (ref "U$2") (pin "4") (pinfunction "4_4") (pintype "passive"))
      (node (ref "U$2") (pin "6") (pinfunction "6_6") (pintype "passive"))
      (node (ref "U$2") (pin "8") (pinfunction "8_8") (pintype "passive"))
      (node (ref "U1") (pin "11") (pinfunction "GND_11") (pintype "power_in"))
      (node (ref "U1") (pin "32") (pinfunction "GND1_32") (pintype "power_in"))
      (node (ref "U1") (pin "62") (pinfunction "GND2_62") (pintype "power_in"))
      (node (ref "U1") (pin "81") (pinfunction "GND3_81") (pintype "power_in"))
      (node (ref "U1") (pin "99") (pinfunction "AGND_99") (pintype "power_in"))
      (node (ref "U2") (pin "7") (pinfunction "GND_7") (pintype "power_in"))
      (node (ref "U3") (pin "1") (pinfunction "GND_1") (pintype "bidirectional"))
      (node (ref "U3") (pin "10") (pinfunction "GND_10") (pintype "bidirectional"))
      (node (ref "U3") (pin "11") (pinfunction "GND_11") (pintype "bidirectional"))
      (node (ref "U3") (pin "19") (pinfunction "SENSE_B_19") (pintype "bidirectional"))
      (node (ref "U3") (pin "2") (pinfunction "SENSE_A_2") (pintype "bidirectional"))
      (node (ref "U3") (pin "20") (pinfunction "GND_20") (pintype "bidirectional"))
      (node (ref "U4") (pin "1") (pinfunction "GND_1") (pintype "bidirectional"))
      (node (ref "U4") (pin "10") (pinfunction "GND_10") (pintype "bidirectional"))
      (node (ref "U4") (pin "11") (pinfunction "GND_11") (pintype "bidirectional"))
      (node (ref "U4") (pin "19") (pinfunction "SENSE_B_19") (pintype "bidirectional"))
      (node (ref "U4") (pin "2") (pinfunction "SENSE_A_2") (pintype "bidirectional"))
      (node (ref "U4") (pin "20") (pinfunction "GND_20") (pintype "bidirectional"))
    )
    (net (code "87") (name "Net-(JP1-DTR)") (class "Default")
      (node (ref "C1") (pin "2") (pinfunction "2_2") (pintype "passive"))
      (node (ref "JP1") (pin "1") (pinfunction "DTR_1") (pintype "passive"))
    )
    (net (code "88") (name "Net-(JP3-Pad2)") (class "Default")
      (node (ref "JP3") (pin "2") (pinfunction "2_2") (pintype "passive"))
      (node (ref "SRV2") (pin "1") (pinfunction "1_1") (pintype "passive"))
      (node (ref "SRV2") (pin "10") (pinfunction "10_10") (pintype "passive"))
      (node (ref "SRV2") (pin "11") (pinfunction "11_11") (pintype "passive"))
      (node (ref "SRV2") (pin "12") (pinfunction "12_12") (pintype "passive"))
      (node (ref "SRV2") (pin "2") (pinfunction "2_2") (pintype "passive"))
      (node (ref "SRV2") (pin "3") (pinfunction "3_3") (pintype "passive"))
      (node (ref "SRV2") (pin "4") (pinfunction "4_4") (pintype "passive"))
      (node (ref "SRV2") (pin "5") (pinfunction "5_5") (pintype "passive"))
      (node (ref "SRV2") (pin "6") (pinfunction "6_6") (pintype "passive"))
      (node (ref "SRV2") (pin "7") (pinfunction "7_7") (pintype "passive"))
      (node (ref "SRV2") (pin "8") (pinfunction "8_8") (pintype "passive"))
      (node (ref "SRV2") (pin "9") (pinfunction "9_9") (pintype "passive"))
    )
    (net (code "89") (name "Net-(U1-AREF)") (class "Default")
      (node (ref "AREF") (pin "1") (pinfunction "1_1") (pintype "passive"))
      (node (ref "C3") (pin "2") (pinfunction "2_2") (pintype "passive"))
      (node (ref "U1") (pin "98") (pinfunction "AREF_98") (pintype "bidirectional"))
    )
    (net (code "90") (name "Net-(U1-AVCC)") (class "Default")
      (node (ref "C15") (pin "1") (pinfunction "1_1") (pintype "passive"))
      (node (ref "L1") (pin "1") (pinfunction "1_1") (pintype "passive"))
      (node (ref "U1") (pin "100") (pinfunction "AVCC_100") (pintype "power_in"))
    )
    (net (code "91") (name "Net-(U1-XTAL1)") (class "Default")
      (node (ref "C10") (pin "1") (pinfunction "1_1") (pintype "passive"))
      (node (ref "U1") (pin "34") (pinfunction "XTAL1_34") (pintype "input"))
      (node (ref "Y1") (pin "2") (pinfunction "2_2") (pintype "passive"))
    )
    (net (code "92") (name "Net-(U1-XTAL2)") (class "Default")
      (node (ref "C9") (pin "1") (pinfunction "1_1") (pintype "passive"))
      (node (ref "U1") (pin "33") (pinfunction "XTAL2_33") (pintype "output"))
      (node (ref "Y1") (pin "1") (pinfunction "1_1") (pintype "passive"))
    )
    (net (code "93") (name "unconnected-(JP1-CTS-Pad5)") (class "Default")
      (node (ref "JP1") (pin "5") (pinfunction "CTS_5") (pintype "passive"))
    )
    (net (code "94") (name "unconnected-(PI-7-GPIO7-Pad7)") (class "Default")
      (node (ref "PI") (pin "7") (pinfunction "7-GPIO7_7") (pintype "bidirectional"))
    )
    (net (code "95") (name "unconnected-(PI-11-GPIO0-Pad11)") (class "Default")
      (node (ref "PI") (pin "11") (pinfunction "11-GPIO0_11") (pintype "bidirectional"))
    )
    (net (code "96") (name "unconnected-(PI-12-GPIO1-Pad12)") (class "Default")
      (node (ref "PI") (pin "12") (pinfunction "12-GPIO1_12") (pintype "bidirectional"))
    )
    (net (code "97") (name "unconnected-(PI-13-GPIO2-Pad13)") (class "Default")
      (node (ref "PI") (pin "13") (pinfunction "13-GPIO2_13") (pintype "bidirectional"))
    )
    (net (code "98") (name "unconnected-(PI-15-GPIO3-Pad15)") (class "Default")
      (node (ref "PI") (pin "15") (pinfunction "15-GPIO3_15") (pintype "bidirectional"))
    )
    (net (code "99") (name "unconnected-(PI-16-GPIO4-Pad16)") (class "Default")
      (node (ref "PI") (pin "16") (pinfunction "16-GPIO4_16") (pintype "bidirectional"))
    )
    (net (code "100") (name "unconnected-(PI-18-GPIO5-Pad18)") (class "Default")
      (node (ref "PI") (pin "18") (pinfunction "18-GPIO5_18") (pintype "bidirectional"))
    )
    (net (code "101") (name "unconnected-(PI-19-SPI-MOSI-Pad19)") (class "Default")
      (node (ref "PI") (pin "19") (pinfunction "19-SPI-MOSI_19") (pintype "bidirectional"))
    )
    (net (code "102") (name "unconnected-(PI-21-SPI-MISO-Pad21)") (class "Default")
      (node (ref "PI") (pin "21") (pinfunction "21-SPI-MISO_21") (pintype "bidirectional"))
    )
    (net (code "103") (name "unconnected-(PI-22-GPIO6-Pad22)") (class "Default")
      (node (ref "PI") (pin "22") (pinfunction "22-GPIO6_22") (pintype "bidirectional"))
    )
    (net (code "104") (name "unconnected-(PI-23-SPI-SCLK-Pad23)") (class "Default")
      (node (ref "PI") (pin "23") (pinfunction "23-SPI-SCLK_23") (pintype "bidirectional"))
    )
    (net (code "105") (name "unconnected-(PI-24-SPI-CE0-N-Pad24)") (class "Default")
      (node (ref "PI") (pin "24") (pinfunction "24-SPI-CE0-N_24") (pintype "bidirectional"))
    )
    (net (code "106") (name "unconnected-(PI-26-SPI-CE1-N-Pad26)") (class "Default")
      (node (ref "PI") (pin "26") (pinfunction "26-SPI-CE1-N_26") (pintype "bidirectional"))
    )
    (net (code "107") (name "unconnected-(U1-(ALE)PG2-Pad70)") (class "Default")
      (node (ref "U1") (pin "70") (pinfunction "(ALE)PG2_70") (pintype "bidirectional"))
    )
    (net (code "108") (name "unconnected-(U1-(OC0A{slash}OC1C{slash}PCINT7)PB7-Pad26)") (class "Default")
      (node (ref "U1") (pin "26") (pinfunction "(OC0A/OC1C/PCINT7)PB7_26") (pintype "bidirectional"))
    )
    (net (code "109") (name "unconnected-(U1-(OC0B)PG5-Pad1)") (class "Default")
      (node (ref "U1") (pin "1") (pinfunction "(OC0B)PG5_1") (pintype "bidirectional"))
    )
    (net (code "110") (name "unconnected-(U1-(OC1A{slash}PCINT5)PB5-Pad24)") (class "Default")
      (node (ref "U1") (pin "24") (pinfunction "(OC1A/PCINT5)PB5_24") (pintype "bidirectional"))
    )
    (net (code "111") (name "unconnected-(U1-(OC1B{slash}PCINT6)PB6-Pad25)") (class "Default")
      (node (ref "U1") (pin "25") (pinfunction "(OC1B/PCINT6)PB6_25") (pintype "bidirectional"))
    )
    (net (code "112") (name "unconnected-(U1-(OC2A{slash}PCINT4)PB4-Pad23)") (class "Default")
      (node (ref "U1") (pin "23") (pinfunction "(OC2A/PCINT4)PB4_23") (pintype "bidirectional"))
    )
    (net (code "113") (name "unconnected-(U1-(RD)PG1-Pad52)") (class "Default")
      (node (ref "U1") (pin "52") (pinfunction "(RD)PG1_52") (pintype "bidirectional"))
    )
    (net (code "114") (name "unconnected-(U1-(SS{slash}PCINT0)PB0-Pad19)") (class "Default")
      (node (ref "U1") (pin "19") (pinfunction "(SS/PCINT0)PB0_19") (pintype "bidirectional"))
    )
    (net (code "115") (name "unconnected-(U1-(TOSC1)PG4-Pad29)") (class "Default")
      (node (ref "U1") (pin "29") (pinfunction "(TOSC1)PG4_29") (pintype "bidirectional"))
    )
    (net (code "116") (name "unconnected-(U1-(TOSC2)PG3-Pad28)") (class "Default")
      (node (ref "U1") (pin "28") (pinfunction "(TOSC2)PG3_28") (pintype "bidirectional"))
    )
    (net (code "117") (name "unconnected-(U1-(WR)PG0-Pad51)") (class "Default")
      (node (ref "U1") (pin "51") (pinfunction "(WR)PG0_51") (pintype "bidirectional"))
    )
    (net (code "118") (name "unconnected-(U1-PH0(RXD2)-Pad12)") (class "Default")
      (node (ref "U1") (pin "12") (pinfunction "PH0(RXD2)_12") (pintype "bidirectional"))
    )
    (net (code "119") (name "unconnected-(U1-PH1(TXD2)-Pad13)") (class "Default")
      (node (ref "U1") (pin "13") (pinfunction "PH1(TXD2)_13") (pintype "bidirectional"))
    )
    (net (code "120") (name "unconnected-(U1-PJ2(XCK3{slash}PCINT11)-Pad65)") (class "Default")
      (node (ref "U1") (pin "65") (pinfunction "PJ2(XCK3/PCINT11)_65") (pintype "bidirectional"))
    )
    (net (code "121") (name "unconnected-(U1-PJ3(PCINT12)-Pad66)") (class "Default")
      (node (ref "U1") (pin "66") (pinfunction "PJ3(PCINT12)_66") (pintype "bidirectional"))
    )
    (net (code "122") (name "unconnected-(U1-PJ4(PCINT13)-Pad67)") (class "Default")
      (node (ref "U1") (pin "67") (pinfunction "PJ4(PCINT13)_67") (pintype "bidirectional"))
    )
    (net (code "123") (name "unconnected-(U1-PJ5(PCINT14)-Pad68)") (class "Default")
      (node (ref "U1") (pin "68") (pinfunction "PJ5(PCINT14)_68") (pintype "bidirectional"))
    )
    (net (code "124") (name "unconnected-(U1-PJ6(PCINT15)-Pad69)") (class "Default")
      (node (ref "U1") (pin "69") (pinfunction "PJ6(PCINT15)_69") (pintype "bidirectional"))
    )
    (net (code "125") (name "unconnected-(U1-PJ7-Pad79)") (class "Default")
      (node (ref "U1") (pin "79") (pinfunction "PJ7_79") (pintype "bidirectional"))
    )
    (net (code "126") (name "unconnected-(U3-NC-Pad3)") (class "Default")
      (node (ref "U3") (pin "3") (pinfunction "NC_3") (pintype "bidirectional"))
    )
    (net (code "127") (name "unconnected-(U3-NC-Pad18)") (class "Default")
      (node (ref "U3") (pin "18") (pinfunction "NC_18") (pintype "bidirectional"))
    )
    (net (code "128") (name "unconnected-(U4-NC-Pad3)") (class "Default")
      (node (ref "U4") (pin "3") (pinfunction "NC_3") (pintype "bidirectional"))
    )
    (net (code "129") (name "unconnected-(U4-NC-Pad18)") (class "Default")
      (node (ref "U4") (pin "18") (pinfunction "NC_18") (pintype "bidirectional"))
    )
  )
)
